# Nucleo_shield.net
KiCad netlist of a schematic drawn in Altium Designer
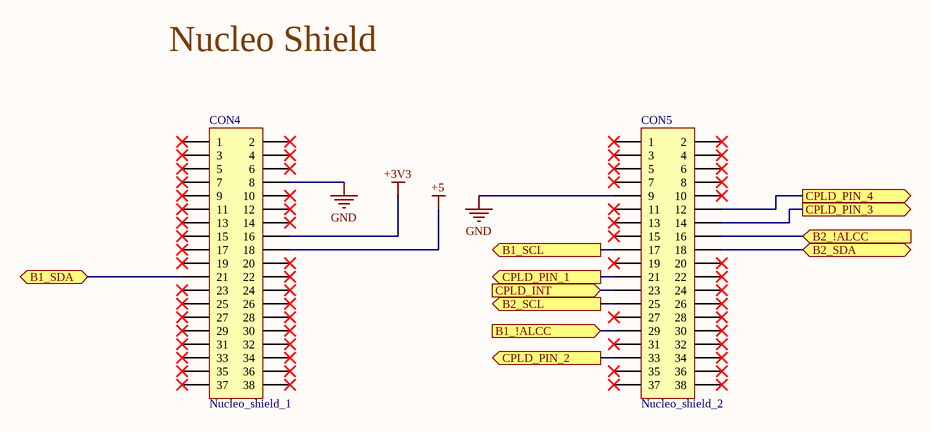
[diagram p0: Nucleo_shield.SchDoc]

(export (version "E")
  (design (tool "Eeschema 10.0.6"))
  (components
    (comp (ref "CON4")
      (value "Nucleo_shield_1")
      (footprint "HDR2X19")
      (description "Header, 19-Pin, Dual row")
      (fields (field (name "PUBLISHER") "Altium Limited"))
      (libsource (lib "BMS_Schematic") (part "Header 19X2"))
    )
    (comp (ref "CON5")
      (value "Nucleo_shield_2")
      (footprint "HDR2X19")
      (description "Header, 19-Pin, Dual row")
      (fields (field (name "PUBLISHER") "Altium Limited"))
      (libsource (lib "BMS_Schematic") (part "Header 19X2"))
    )
  )
  (nets
    (net (code "1") (name "+3V3") (class "Default")
      (node (ref "CON4") (pin "16") (pinfunction "16_16") (pintype "passive"))
    )
    (net (code "2") (name "+5") (class "Default")
      (node (ref "CON4") (pin "18") (pinfunction "18_18") (pintype "passive"))
    )
    (net (code "3") (name "/B1_!ALCC") (class "Default")
      (node (ref "CON5") (pin "29") (pinfunction "29_29") (pintype "passive"))
    )
    (net (code "4") (name "/B1_SCL") (class "Default")
      (node (ref "CON5") (pin "17") (pinfunction "17_17") (pintype "passive"))
    )
    (net (code "5") (name "/B1_SDA") (class "Default")
      (node (ref "CON4") (pin "21") (pinfunction "21_21") (pintype "passive"))
    )
    (net (code "6") (name "/B2_!ALCC") (class "Default")
      (node (ref "CON5") (pin "16") (pinfunction "16_16") (pintype "passive"))
    )
    (net (code "7") (name "/B2_SCL") (class "Default")
      (node (ref "CON5") (pin "25") (pinfunction "25_25") (pintype "passive"))
    )
    (net (code "8") (name "/B2_SDA") (class "Default")
      (node (ref "CON5") (pin "18") (pinfunction "18_18") (pintype "passive"))
    )
    (net (code "9") (name "/CPLD_INT") (class "Default")
      (node (ref "CON5") (pin "23") (pinfunction "23_23") (pintype "passive"))
    )
    (net (code "10") (name "/CPLD_PIN_1") (class "Default")
      (node (ref "CON5") (pin "21") (pinfunction "21_21") (pintype "passive"))
    )
    (net (code "11") (name "/CPLD_PIN_2") (class "Default")
      (node (ref "CON5") (pin "33") (pinfunction "33_33") (pintype "passive"))
    )
    (net (code "12") (name "/CPLD_PIN_3") (class "Default")
      (node (ref "CON5") (pin "14") (pinfunction "14_14") (pintype "passive"))
    )
    (net (code "13") (name "/CPLD_PIN_4") (class "Default")
      (node (ref "CON5") (pin "12") (pinfunction "12_12") (pintype "passive"))
    )
    (net (code "14") (name "GND") (class "Default")
      (node (ref "CON4") (pin "8") (pinfunction "8_8") (pintype "passive"))
      (node (ref "CON5") (pin "9") (pinfunction "9_9") (pintype "passive"))
    )
    (net (code "15") (name "unconnected-(CON4-Pad1)") (class "Default")
      (node (ref "CON4") (pin "1") (pinfunction "1_1") (pintype "passive+no_connect"))
    )
    (net (code "16") (name "unconnected-(CON4-Pad2)") (class "Default")
      (node (ref "CON4") (pin "2") (pinfunction "2_2") (pintype "passive+no_connect"))
    )
    (net (code "17") (name "unconnected-(CON4-Pad3)") (class "Default")
      (node (ref "CON4") (pin "3") (pinfunction "3_3") (pintype "passive+no_connect"))
    )
    (net (code "18") (name "unconnected-(CON4-Pad4)") (class "Default")
      (node (ref "CON4") (pin "4") (pinfunction "4_4") (pintype "passive+no_connect"))
    )
    (net (code "19") (name "unconnected-(CON4-Pad5)") (class "Default")
      (node (ref "CON4") (pin "5") (pinfunction "5_5") (pintype "passive+no_connect"))
    )
    (net (code "20") (name "unconnected-(CON4-Pad6)") (class "Default")
      (node (ref "CON4") (pin "6") (pinfunction "6_6") (pintype "passive+no_connect"))
    )
    (net (code "21") (name "unconnected-(CON4-Pad7)") (class "Default")
      (node (ref "CON4") (pin "7") (pinfunction "7_7") (pintype "passive+no_connect"))
    )
    (net (code "22") (name "unconnected-(CON4-Pad9)") (class "Default")
      (node (ref "CON4") (pin "9") (pinfunction "9_9") (pintype "passive+no_connect"))
    )
    (net (code "23") (name "unconnected-(CON4-Pad10)") (class "Default")
      (node (ref "CON4") (pin "10") (pinfunction "10_10") (pintype "passive+no_connect"))
    )
    (net (code "24") (name "unconnected-(CON4-Pad11)") (class "Default")
      (node (ref "CON4") (pin "11") (pinfunction "11_11") (pintype "passive+no_connect"))
    )
    (net (code "25") (name "unconnected-(CON4-Pad12)") (class "Default")
      (node (ref "CON4") (pin "12") (pinfunction "12_12") (pintype "passive+no_connect"))
    )
    (net (code "26") (name "unconnected-(CON4-Pad13)") (class "Default")
      (node (ref "CON4") (pin "13") (pinfunction "13_13") (pintype "passive+no_connect"))
    )
    (net (code "27") (name "unconnected-(CON4-Pad14)") (class "Default")
      (node (ref "CON4") (pin "14") (pinfunction "14_14") (pintype "passive+no_connect"))
    )
    (net (code "28") (name "unconnected-(CON4-Pad15)") (class "Default")
      (node (ref "CON4") (pin "15") (pinfunction "15_15") (pintype "passive+no_connect"))
    )
    (net (code "29") (name "unconnected-(CON4-Pad17)") (class "Default")
      (node (ref "CON4") (pin "17") (pinfunction "17_17") (pintype "passive+no_connect"))
    )
    (net (code "30") (name "unconnected-(CON4-Pad19)") (class "Default")
      (node (ref "CON4") (pin "19") (pinfunction "19_19") (pintype "passive+no_connect"))
    )
    (net (code "31") (name "unconnected-(CON4-Pad20)") (class "Default")
      (node (ref "CON4") (pin "20") (pinfunction "20_20") (pintype "passive+no_connect"))
    )
    (net (code "32") (name "unconnected-(CON4-Pad22)") (class "Default")
      (node (ref "CON4") (pin "22") (pinfunction "22_22") (pintype "passive+no_connect"))
    )
    (net (code "33") (name "unconnected-(CON4-Pad23)") (class "Default")
      (node (ref "CON4") (pin "23") (pinfunction "23_23") (pintype "passive+no_connect"))
    )
    (net (code "34") (name "unconnected-(CON4-Pad24)") (class "Default")
      (node (ref "CON4") (pin "24") (pinfunction "24_24") (pintype "passive+no_connect"))
    )
    (net (code "35") (name "unconnected-(CON4-Pad25)") (class "Default")
      (node (ref "CON4") (pin "25") (pinfunction "25_25") (pintype "passive+no_connect"))
    )
    (net (code "36") (name "unconnected-(CON4-Pad26)") (class "Default")
      (node (ref "CON4") (pin "26") (pinfunction "26_26") (pintype "passive+no_connect"))
    )
    (net (code "37") (name "unconnected-(CON4-Pad27)") (class "Default")
      (node (ref "CON4") (pin "27") (pinfunction "27_27") (pintype "passive+no_connect"))
    )
    (net (code "38") (name "unconnected-(CON4-Pad28)") (class "Default")
      (node (ref "CON4") (pin "28") (pinfunction "28_28") (pintype "passive+no_connect"))
    )
    (net (code "39") (name "unconnected-(CON4-Pad29)") (class "Default")
      (node (ref "CON4") (pin "29") (pinfunction "29_29") (pintype "passive+no_connect"))
    )
    (net (code "40") (name "unconnected-(CON4-Pad30)") (class "Default")
      (node (ref "CON4") (pin "30") (pinfunction "30_30") (pintype "passive+no_connect"))
    )
    (net (code "41") (name "unconnected-(CON4-Pad31)") (class "Default")
      (node (ref "CON4") (pin "31") (pinfunction "31_31") (pintype "passive+no_connect"))
    )
    (net (code "42") (name "unconnected-(CON4-Pad32)") (class "Default")
      (node (ref "CON4") (pin "32") (pinfunction "32_32") (pintype "passive+no_connect"))
    )
    (net (code "43") (name "unconnected-(CON4-Pad33)") (class "Default")
      (node (ref "CON4") (pin "33") (pinfunction "33_33") (pintype "passive+no_connect"))
    )
    (net (code "44") (name "unconnected-(CON4-Pad34)") (class "Default")
      (node (ref "CON4") (pin "34") (pinfunction "34_34") (pintype "passive+no_connect"))
    )
    (net (code "45") (name "unconnected-(CON4-Pad35)") (class "Default")
      (node (ref "CON4") (pin "35") (pinfunction "35_35") (pintype "passive+no_connect"))
    )
    (net (code "46") (name "unconnected-(CON4-Pad36)") (class "Default")
      (node (ref "CON4") (pin "36") (pinfunction "36_36") (pintype "passive+no_connect"))
    )
    (net (code "47") (name "unconnected-(CON4-Pad37)") (class "Default")
      (node (ref "CON4") (pin "37") (pinfunction "37_37") (pintype "passive+no_connect"))
    )
    (net (code "48") (name "unconnected-(CON4-Pad38)") (class "Default")
      (node (ref "CON4") (pin "38") (pinfunction "38_38") (pintype "passive+no_connect"))
    )
    (net (code "49") (name "unconnected-(CON5-Pad1)") (class "Default")
      (node (ref "CON5") (pin "1") (pinfunction "1_1") (pintype "passive+no_connect"))
    )
    (net (code "50") (name "unconnected-(CON5-Pad2)") (class "Default")
      (node (ref "CON5") (pin "2") (pinfunction "2_2") (pintype "passive+no_connect"))
    )
    (net (code "51") (name "unconnected-(CON5-Pad3)") (class "Default")
      (node (ref "CON5") (pin "3") (pinfunction "3_3") (pintype "passive+no_connect"))
    )
    (net (code "52") (name "unconnected-(CON5-Pad4)") (class "Default")
      (node (ref "CON5") (pin "4") (pinfunction "4_4") (pintype "passive+no_connect"))
    )
    (net (code "53") (name "unconnected-(CON5-Pad5)") (class "Default")
      (node (ref "CON5") (pin "5") (pinfunction "5_5") (pintype "passive+no_connect"))
    )
    (net (code "54") (name "unconnected-(CON5-Pad6)") (class "Default")
      (node (ref "CON5") (pin "6") (pinfunction "6_6") (pintype "passive+no_connect"))
    )
    (net (code "55") (name "unconnected-(CON5-Pad7)") (class "Default")
      (node (ref "CON5") (pin "7") (pinfunction "7_7") (pintype "passive+no_connect"))
    )
    (net (code "56") (name "unconnected-(CON5-Pad8)") (class "Default")
      (node (ref "CON5") (pin "8") (pinfunction "8_8") (pintype "passive+no_connect"))
    )
    (net (code "57") (name "unconnected-(CON5-Pad10)") (class "Default")
      (node (ref "CON5") (pin "10") (pinfunction "10_10") (pintype "passive+no_connect"))
    )
    (net (code "58") (name "unconnected-(CON5-Pad11)") (class "Default")
      (node (ref "CON5") (pin "11") (pinfunction "11_11") (pintype "passive+no_connect"))
    )
    (net (code "59") (name "unconnected-(CON5-Pad13)") (class "Default")
      (node (ref "CON5") (pin "13") (pinfunction "13_13") (pintype "passive+no_connect"))
    )
    (net (code "60") (name "unconnected-(CON5-Pad15)") (class "Default")
      (node (ref "CON5") (pin "15") (pinfunction "15_15") (pintype "passive+no_connect"))
    )
    (net (code "61") (name "unconnected-(CON5-Pad19)") (class "Default")
      (node (ref "CON5") (pin "19") (pinfunction "19_19") (pintype "passive+no_connect"))
    )
    (net (code "62") (name "unconnected-(CON5-Pad20)") (class "Default")
      (node (ref "CON5") (pin "20") (pinfunction "20_20") (pintype "passive+no_connect"))
    )
    (net (code "63") (name "unconnected-(CON5-Pad22)") (class "Default")
      (node (ref "CON5") (pin "22") (pinfunction "22_22") (pintype "passive+no_connect"))
    )
    (net (code "64") (name "unconnected-(CON5-Pad24)") (class "Default")
      (node (ref "CON5") (pin "24") (pinfunction "24_24") (pintype "passive+no_connect"))
    )
    (net (code "65") (name "unconnected-(CON5-Pad26)") (class "Default")
      (node (ref "CON5") (pin "26") (pinfunction "26_26") (pintype "passive+no_connect"))
    )
    (net (code "66") (name "unconnected-(CON5-Pad27)") (class "Default")
      (node (ref "CON5") (pin "27") (pinfunction "27_27") (pintype "passive+no_connect"))
    )
    (net (code "67") (name "unconnected-(CON5-Pad28)") (class "Default")
      (node (ref "CON5") (pin "28") (pinfunction "28_28") (pintype "passive+no_connect"))
    )
    (net (code "68") (name "unconnected-(CON5-Pad30)") (class "Default")
      (node (ref "CON5") (pin "30") (pinfunction "30_30") (pintype "passive+no_connect"))
    )
    (net (code "69") (name "unconnected-(CON5-Pad31)") (class "Default")
      (node (ref "CON5") (pin "31") (pinfunction "31_31") (pintype "passive+no_connect"))
    )
    (net (code "70") (name "unconnected-(CON5-Pad32)") (class "Default")
      (node (ref "CON5") (pin "32") (pinfunction "32_32") (pintype "passive+no_connect"))
    )
    (net (code "71") (name "unconnected-(CON5-Pad34)") (class "Default")
      (node (ref "CON5") (pin "34") (pinfunction "34_34") (pintype "passive+no_connect"))
    )
    (net (code "72") (name "unconnected-(CON5-Pad35)") (class "Default")
      (node (ref "CON5") (pin "35") (pinfunction "35_35") (pintype "passive+no_connect"))
    )
    (net (code "73") (name "unconnected-(CON5-Pad36)") (class "Default")
      (node (ref "CON5") (pin "36") (pinfunction "36_36") (pintype "passive+no_connect"))
    )
    (net (code "74") (name "unconnected-(CON5-Pad37)") (class "Default")
      (node (ref "CON5") (pin "37") (pinfunction "37_37") (pintype "passive+no_connect"))
    )
    (net (code "75") (name "unconnected-(CON5-Pad38)") (class "Default")
      (node (ref "CON5") (pin "38") (pinfunction "38_38") (pintype "passive+no_connect"))
    )
  )
)
